# april-demo.net
KiCad netlist of a schematic drawn in Altium Designer
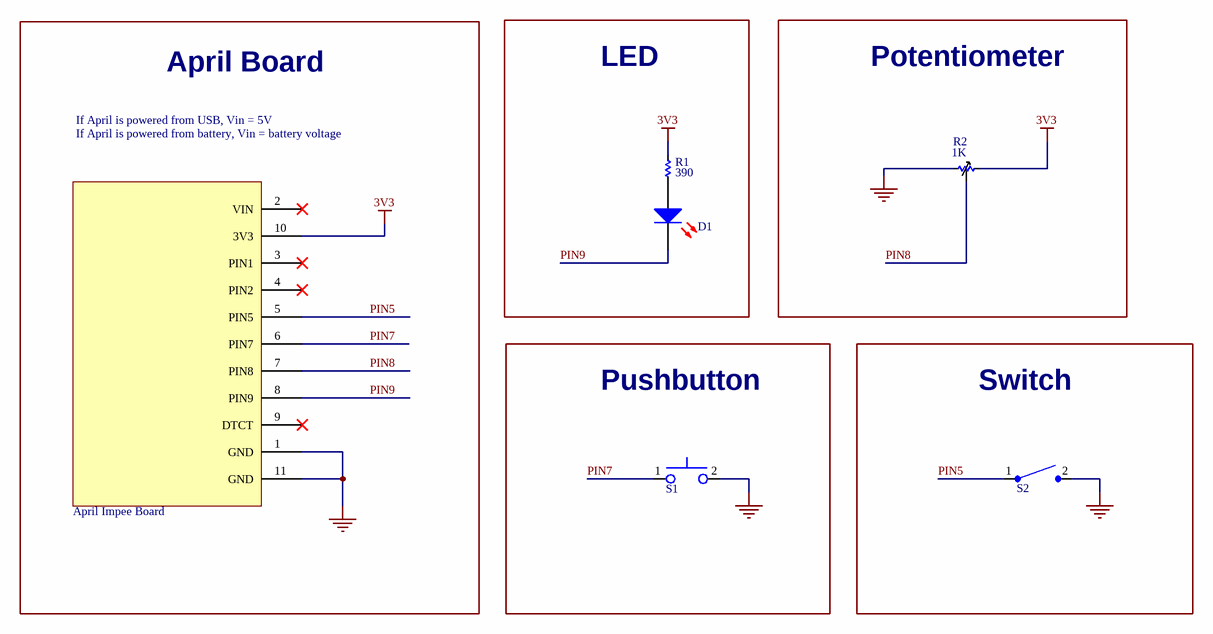
[diagram p0: april-demo.SchDoc]

(export (version "E")
  (design (tool "Eeschema 10.0.6"))
  (components
    (comp (ref "D1") (value "LED Red") (libsource (lib "imp-schlib") (part "LED_RED")))
    (comp (ref "J1")
      (value "April Impee Board")
      (description "Electric Imp Breakout Board with Voltage Regulator")
      (fields
        (field (name "MANUFACTURER") "Electric Imp")
        (field (name "MANUFACTURER PART NUMBER") "Impee April")
      )
      (libsource (lib "imp-schlib-tom") (part "APRIL"))
    )
    (comp (ref "R1") (value "390") (description "Resistor") (libsource (lib "imp-schlib") (part "RES")))
    (comp (ref "R2") (value "1K") (description "Potentiometer") (libsource (lib "imp-schlib") (part "POT")))
    (comp (ref "S1")
      (value "BUTTON")
      (description "SWITCH, PUSHBUTTON, NOMINALLY OFF")
      (libsource (lib "imp-schlib-tom") (part "BTN-MOMENTARY"))
    )
    (comp (ref "S2")
      (value "SWITCH")
      (description "Switch, SPST, On-Off")
      (libsource (lib "imp-schlib-tom") (part "SW-SPST-ON-OFF"))
    )
  )
  (nets
    (net (code "1") (name "/PIN5") (class "Default")
      (node (ref "J1") (pin "5") (pinfunction "PIN5_5") (pintype "passive"))
      (node (ref "S2") (pin "1") (pinfunction "PIN1_1") (pintype "passive"))
    )
    (net (code "2") (name "/PIN7") (class "Default")
      (node (ref "J1") (pin "6") (pinfunction "PIN7_6") (pintype "passive"))
      (node (ref "S1") (pin "1") (pinfunction "PIN1_1") (pintype "passive"))
    )
    (net (code "3") (name "/PIN8") (class "Default")
      (node (ref "J1") (pin "7") (pinfunction "PIN8_7") (pintype "passive"))
      (node (ref "R2") (pin "2") (pinfunction "2_2") (pintype "passive"))
    )
    (net (code "4") (name "/PIN9") (class "Default")
      (node (ref "D1") (pin "K") (pinfunction "K_K") (pintype "passive"))
      (node (ref "J1") (pin "8") (pinfunction "PIN9_8") (pintype "passive"))
    )
    (net (code "5") (name "3V3") (class "Default")
      (node (ref "J1") (pin "10") (pinfunction "3V3_10") (pintype "passive"))
      (node (ref "R1") (pin "2") (pinfunction "2_2") (pintype "passive"))
      (node (ref "R2") (pin "3") (pinfunction "3_3") (pintype "passive"))
    )
    (net (code "6") (name "GND") (class "Default")
      (node (ref "J1") (pin "1") (pinfunction "GND_1") (pintype "passive"))
      (node (ref "J1") (pin "11") (pinfunction "GND_11") (pintype "passive"))
      (node (ref "R2") (pin "1") (pinfunction "1_1") (pintype "passive"))
      (node (ref "S1") (pin "2") (pinfunction "PIN2_2") (pintype "passive"))
      (node (ref "S2") (pin "2") (pinfunction "PIN2_2") (pintype "passive"))
    )
    (net (code "7") (name "Net-(D1-PadA)") (class "Default")
      (node (ref "D1") (pin "A") (pinfunction "A_A") (pintype "passive"))
      (node (ref "R1") (pin "1") (pinfunction "1_1") (pintype "passive"))
    )
    (net (code "8") (name "unconnected-(J1-DTCT-Pad9)") (class "Default")
      (node (ref "J1") (pin "9") (pinfunction "DTCT_9") (pintype "passive+no_connect"))
    )
    (net (code "9") (name "unconnected-(J1-PIN1-Pad3)") (class "Default")
      (node (ref "J1") (pin "3") (pinfunction "PIN1_3") (pintype "passive+no_connect"))
    )
    (net (code "10") (name "unconnected-(J1-PIN2-Pad4)") (class "Default")
      (node (ref "J1") (pin "4") (pinfunction "PIN2_4") (pintype "passive+no_connect"))
    )
    (net (code "11") (name "unconnected-(J1-VIN-Pad2)") (class "Default")
      (node (ref "J1") (pin "2") (pinfunction "VIN_2") (pintype "passive+no_connect"))
    )
  )
)
